# vehicle.net
KiCad netlist of a schematic drawn in Altium Designer
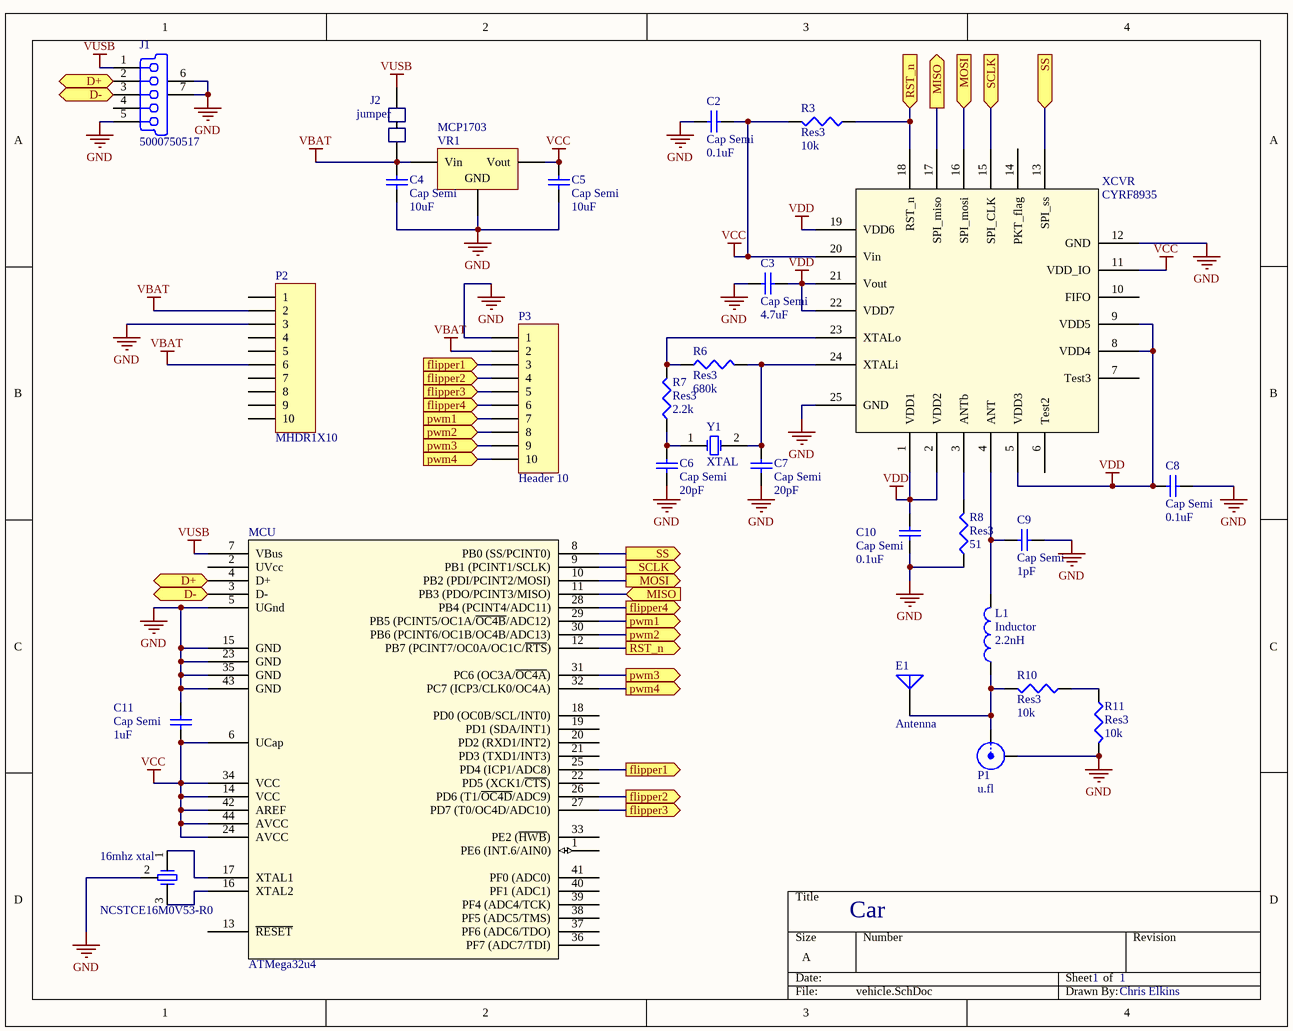
[diagram p0: vehicle.SchDoc]

(export (version "E")
  (design (tool "Eeschema 10.0.6"))
  (components
    (comp (ref "16mhz xtal")
      (value "NCSTCE16M0V53-R0")
      (footprint "OSC")
      (libsource (lib "Integrated_Library1") (part "NCSTCE16M0V53-R0"))
    )
    (comp (ref "C2")
      (value "Cap Semi")
      (footprint "CAPC1608L")
      (description "Capacitor (Semiconductor SIM Model)")
      (fields (field (name "ALTIUM_VALUE") "0.1uF") (field (name "PUBLISHER") "Altium Limited"))
      (libsource (lib "Miscellaneous Devices") (part "Cap Semi"))
    )
    (comp (ref "C3")
      (value "Cap Semi")
      (footprint "CAPC1608L")
      (description "Capacitor (Semiconductor SIM Model)")
      (fields (field (name "ALTIUM_VALUE") "4.7uF") (field (name "PUBLISHER") "Altium Limited"))
      (libsource (lib "Miscellaneous Devices") (part "Cap Semi"))
    )
    (comp (ref "C4")
      (value "Cap Semi")
      (footprint "CAPC1608L")
      (description "Capacitor (Semiconductor SIM Model)")
      (fields (field (name "ALTIUM_VALUE") "10uF") (field (name "PUBLISHER") "Altium Limited"))
      (libsource (lib "Miscellaneous Devices") (part "Cap Semi"))
    )
    (comp (ref "C5")
      (value "Cap Semi")
      (footprint "CAPC1608L")
      (description "Capacitor (Semiconductor SIM Model)")
      (fields (field (name "ALTIUM_VALUE") "10uF") (field (name "PUBLISHER") "Altium Limited"))
      (libsource (lib "Miscellaneous Devices") (part "Cap Semi"))
    )
    (comp (ref "C6")
      (value "Cap Semi")
      (footprint "CAPC1608L")
      (description "Capacitor (Semiconductor SIM Model)")
      (fields (field (name "ALTIUM_VALUE") "20pF") (field (name "PUBLISHER") "Altium Limited"))
      (libsource (lib "Miscellaneous Devices") (part "Cap Semi"))
    )
    (comp (ref "C7")
      (value "Cap Semi")
      (footprint "CAPC1608L")
      (description "Capacitor (Semiconductor SIM Model)")
      (fields (field (name "ALTIUM_VALUE") "20pF") (field (name "PUBLISHER") "Altium Limited"))
      (libsource (lib "Miscellaneous Devices") (part "Cap Semi"))
    )
    (comp (ref "C8")
      (value "Cap Semi")
      (footprint "CAPC1608L")
      (description "Capacitor (Semiconductor SIM Model)")
      (fields (field (name "ALTIUM_VALUE") "0.1uF") (field (name "PUBLISHER") "Altium Limited"))
      (libsource (lib "Miscellaneous Devices") (part "Cap Semi"))
    )
    (comp (ref "C9")
      (value "Cap Semi")
      (footprint "CAPC1608L")
      (description "Capacitor (Semiconductor SIM Model)")
      (fields (field (name "ALTIUM_VALUE") "1pF") (field (name "PUBLISHER") "Altium Limited"))
      (libsource (lib "Miscellaneous Devices") (part "Cap Semi"))
    )
    (comp (ref "C10")
      (value "Cap Semi")
      (footprint "CAPC1608L")
      (description "Capacitor (Semiconductor SIM Model)")
      (fields (field (name "ALTIUM_VALUE") "0.1uF") (field (name "PUBLISHER") "Altium Limited"))
      (libsource (lib "Miscellaneous Devices") (part "Cap Semi"))
    )
    (comp (ref "C11")
      (value "Cap Semi")
      (footprint "CAPC1608L")
      (description "Capacitor (Semiconductor SIM Model)")
      (fields (field (name "ALTIUM_VALUE") "1uF") (field (name "PUBLISHER") "Altium Limited"))
      (libsource (lib "Miscellaneous Devices") (part "Cap Semi"))
    )
    (comp (ref "E1")
      (value "Antenna")
      (footprint "PIN1")
      (description "Generic Antenna")
      (fields (field (name "PUBLISHER") "Altium Limited"))
      (libsource (lib "Miscellaneous Devices") (part "Antenna"))
    )
    (comp (ref "J1")
      (value "5000750517")
      (footprint "HDR1X4")
      (fields (field (name "PUBLISHER") "Altium Limited"))
      (libsource (lib "Molex Serial Bus Mini USB") (part "5000750517"))
    )
    (comp (ref "J2")
      (value "jumper")
      (footprint "jumper pad")
      (libsource (lib "Integrated_Library1") (part "solder jumper"))
    )
    (comp (ref "L1")
      (value "Inductor")
      (footprint "INDC1608L")
      (fields (field (name "ALTIUM_VALUE") "2.2nH") (field (name "PUBLISHER") "Altium Limited"))
      (libsource (lib "Miscellaneous Devices") (part "Inductor"))
    )
    (comp (ref "MCU")
      (value "ATMega32u4")
      (footprint "TQFP44_M")
      (description "usb enabled avr microcontroller")
      (libsource (lib "Integrated_Library1") (part "ATMega32u4"))
    )
    (comp (ref "P1")
      (value "u.fl")
      (footprint "U.FL connector")
      (description "BNC Elbow Connector")
      (fields (field (name "PUBLISHER") "Altium Limited"))
      (libsource (lib "Miscellaneous Connectors") (part "BNC"))
    )
    (comp (ref "P2")
      (value "MHDR1X10")
      (footprint "MHDR1X10")
      (description "Header, 10-Pin")
      (fields (field (name "PUBLISHER") "Altium Limited"))
      (libsource (lib "Miscellaneous Connectors") (part "MHDR1X10"))
    )
    (comp (ref "P3")
      (value "Header 10")
      (footprint "HDR1X10")
      (description "Header, 10-Pin")
      (fields (field (name "PUBLISHER") "Altium Limited"))
      (libsource (lib "Miscellaneous Connectors") (part "Header 10"))
    )
    (comp (ref "R3")
      (value "Res3")
      (footprint "RESC1608L")
      (description "Resistor")
      (fields (field (name "ALTIUM_VALUE") "10k") (field (name "PUBLISHER") "Altium Limited"))
      (libsource (lib "Miscellaneous Devices") (part "Res3"))
    )
    (comp (ref "R6")
      (value "Res3")
      (footprint "RESC1608L")
      (description "Resistor")
      (fields (field (name "ALTIUM_VALUE") "680k") (field (name "PUBLISHER") "Altium Limited"))
      (libsource (lib "Miscellaneous Devices") (part "Res3"))
    )
    (comp (ref "R7")
      (value "Res3")
      (footprint "RESC1608L")
      (description "Resistor")
      (fields (field (name "ALTIUM_VALUE") "2.2k") (field (name "PUBLISHER") "Altium Limited"))
      (libsource (lib "Miscellaneous Devices") (part "Res3"))
    )
    (comp (ref "R8")
      (value "Res3")
      (footprint "RESC1608L")
      (description "Resistor")
      (fields (field (name "ALTIUM_VALUE") "51") (field (name "PUBLISHER") "Altium Limited"))
      (libsource (lib "Miscellaneous Devices") (part "Res3"))
    )
    (comp (ref "R10")
      (value "Res3")
      (footprint "RESC1608L")
      (description "Resistor")
      (fields (field (name "ALTIUM_VALUE") "10k") (field (name "PUBLISHER") "Altium Limited"))
      (libsource (lib "Miscellaneous Devices") (part "Res3"))
    )
    (comp (ref "R11")
      (value "Res3")
      (footprint "RESC1608L")
      (description "Resistor")
      (fields (field (name "ALTIUM_VALUE") "10k") (field (name "PUBLISHER") "Altium Limited"))
      (libsource (lib "Miscellaneous Devices") (part "Res3"))
    )
    (comp (ref "VR1")
      (value "MCP1703")
      (footprint "SOT223-4N")
      (description "Voltage Regulator")
      (fields (field (name "PUBLISHER") "Altium Limited"))
      (libsource (lib "Miscellaneous Devices") (part "Volt Reg"))
    )
    (comp (ref "XCVR")
      (value "CYRF8935")
      (footprint "QFN50P400X400-24VAL")
      (libsource (lib "Integrated_Library1") (part "CYRF8935"))
    )
    (comp (ref "Y1")
      (value "XTAL")
      (footprint "PCBComponent_1")
      (description "Crystal Oscillator")
      (fields (field (name "PUBLISHER") "Altium Limited"))
      (libsource (lib "Miscellaneous Devices") (part "XTAL"))
    )
  )
  (nets
    (net (code "1") (name "/D+") (class "Default")
      (node (ref "J1") (pin "2") (pinfunction "D-_2") (pintype "passive"))
      (node (ref "MCU") (pin "4") (pinfunction "D+_4") (pintype "passive"))
    )
    (net (code "2") (name "/D-") (class "Default")
      (node (ref "J1") (pin "3") (pinfunction "D+_3") (pintype "passive"))
      (node (ref "MCU") (pin "3") (pinfunction "D-_3") (pintype "passive"))
    )
    (net (code "3") (name "/MISO") (class "Default")
      (node (ref "MCU") (pin "11") (pinfunction "PB3_(PDO/PCINT3/MISO)_11") (pintype "passive"))
      (node (ref "XCVR") (pin "17") (pinfunction "SPI_miso_17") (pintype "passive"))
    )
    (net (code "4") (name "/MOSI") (class "Default")
      (node (ref "MCU") (pin "10") (pinfunction "PB2_(PDI/PCINT2/MOSI)_10") (pintype "passive"))
      (node (ref "XCVR") (pin "16") (pinfunction "SPI_mosi_16") (pintype "passive"))
    )
    (net (code "5") (name "/RST_n") (class "Default")
      (node (ref "MCU") (pin "12") (pinfunction "PB7_(PCINT7/OC0A/OC1C/~{RTS})_12") (pintype "passive"))
      (node (ref "R3") (pin "1") (pinfunction "1_1") (pintype "passive"))
      (node (ref "XCVR") (pin "18") (pinfunction "RST_n_18") (pintype "passive"))
    )
    (net (code "6") (name "/SCLK") (class "Default")
      (node (ref "MCU") (pin "9") (pinfunction "PB1_(PCINT1/SCLK)_9") (pintype "passive"))
      (node (ref "XCVR") (pin "15") (pinfunction "SPI_CLK_15") (pintype "passive"))
    )
    (net (code "7") (name "/SS") (class "Default")
      (node (ref "MCU") (pin "8") (pinfunction "PB0_(SS/PCINT0)_8") (pintype "passive"))
      (node (ref "XCVR") (pin "13") (pinfunction "SPI_ss_13") (pintype "passive"))
    )
    (net (code "8") (name "/flipper1") (class "Default")
      (node (ref "MCU") (pin "25") (pinfunction "PD4_(ICP1/ADC8)_25") (pintype "passive"))
      (node (ref "P3") (pin "3") (pinfunction "3_3") (pintype "passive"))
    )
    (net (code "9") (name "/flipper2") (class "Default")
      (node (ref "MCU") (pin "26") (pinfunction "PD6_(T1/~{OC4D}/ADC9)_26") (pintype "passive"))
      (node (ref "P3") (pin "4") (pinfunction "4_4") (pintype "passive"))
    )
    (net (code "10") (name "/flipper3") (class "Default")
      (node (ref "MCU") (pin "27") (pinfunction "PD7_(T0/OC4D/ADC10)_27") (pintype "passive"))
      (node (ref "P3") (pin "5") (pinfunction "5_5") (pintype "passive"))
    )
    (net (code "11") (name "/flipper4") (class "Default")
      (node (ref "MCU") (pin "28") (pinfunction "PB4_(PCINT4/ADC11)_28") (pintype "passive"))
      (node (ref "P3") (pin "6") (pinfunction "6_6") (pintype "passive"))
    )
    (net (code "12") (name "/pwm1") (class "Default")
      (node (ref "MCU") (pin "29") (pinfunction "PB5_(PCINT5/OC1A/~{OC4B}/ADC12)_29") (pintype "passive"))
      (node (ref "P3") (pin "7") (pinfunction "7_7") (pintype "passive"))
    )
    (net (code "13") (name "/pwm2") (class "Default")
      (node (ref "MCU") (pin "30") (pinfunction "PB6_(PCINT6/OC1B/OC4B/ADC13)_30") (pintype "passive"))
      (node (ref "P3") (pin "8") (pinfunction "8_8") (pintype "passive"))
    )
    (net (code "14") (name "/pwm3") (class "Default")
      (node (ref "MCU") (pin "31") (pinfunction "PC6_(OC3A/~{OC4A})_31") (pintype "passive"))
      (node (ref "P3") (pin "9") (pinfunction "9_9") (pintype "passive"))
    )
    (net (code "15") (name "/pwm4") (class "Default")
      (node (ref "MCU") (pin "32") (pinfunction "PC7_(ICP3/CLK0/OC4A)_32") (pintype "passive"))
      (node (ref "P3") (pin "10") (pinfunction "10_10") (pintype "passive"))
    )
    (net (code "16") (name "GND") (class "Default")
      (node (ref "16mhz xtal") (pin "2") (pintype "passive"))
      (node (ref "C10") (pin "2") (pinfunction "2_2") (pintype "passive"))
      (node (ref "C11") (pin "2") (pinfunction "2_2") (pintype "passive"))
      (node (ref "C2") (pin "1") (pinfunction "1_1") (pintype "passive"))
      (node (ref "C3") (pin "1") (pinfunction "1_1") (pintype "passive"))
      (node (ref "C4") (pin "1") (pinfunction "1_1") (pintype "passive"))
      (node (ref "C5") (pin "1") (pinfunction "1_1") (pintype "passive"))
      (node (ref "C6") (pin "1") (pinfunction "1_1") (pintype "passive"))
      (node (ref "C7") (pin "1") (pinfunction "1_1") (pintype "passive"))
      (node (ref "C8") (pin "1") (pinfunction "1_1") (pintype "passive"))
      (node (ref "C9") (pin "2") (pinfunction "2_2") (pintype "passive"))
      (node (ref "J1") (pin "5") (pinfunction "GND_5") (pintype "passive"))
      (node (ref "J1") (pin "6") (pinfunction "MH1_6") (pintype "passive"))
      (node (ref "J1") (pin "7") (pinfunction "MH2_7") (pintype "passive"))
      (node (ref "MCU") (pin "15") (pinfunction "GND_15") (pintype "passive"))
      (node (ref "MCU") (pin "23") (pinfunction "GND_23") (pintype "passive"))
      (node (ref "MCU") (pin "35") (pinfunction "GND_35") (pintype "passive"))
      (node (ref "MCU") (pin "43") (pinfunction "GND_43") (pintype "passive"))
      (node (ref "MCU") (pin "5") (pinfunction "UGnd_5") (pintype "passive"))
      (node (ref "P1") (pin "2") (pinfunction "Y_2") (pintype "passive"))
      (node (ref "P2") (pin "3") (pinfunction "3_3") (pintype "passive"))
      (node (ref "P3") (pin "1") (pinfunction "1_1") (pintype "passive"))
      (node (ref "R11") (pin "2") (pinfunction "2_2") (pintype "passive"))
      (node (ref "R8") (pin "1") (pinfunction "1_1") (pintype "passive"))
      (node (ref "VR1") (pin "2") (pinfunction "GND_2") (pintype "passive"))
      (node (ref "XCVR") (pin "12") (pinfunction "GND_12") (pintype "passive"))
      (node (ref "XCVR") (pin "25") (pinfunction "GND_25") (pintype "passive"))
    )
    (net (code "17") (name "Net-(E1-A)") (class "Default")
      (node (ref "E1") (pin "1") (pinfunction "A_1") (pintype "passive"))
      (node (ref "L1") (pin "1") (pinfunction "1_1") (pintype "passive"))
      (node (ref "P1") (pin "1") (pinfunction "X_1") (pintype "passive"))
      (node (ref "R10") (pin "2") (pinfunction "2_2") (pintype "passive"))
    )
    (net (code "18") (name "Net-(MCU-XTAL1)") (class "Default")
      (node (ref "16mhz xtal") (pin "1") (pintype "passive"))
      (node (ref "MCU") (pin "17") (pinfunction "XTAL1_17") (pintype "passive"))
    )
    (net (code "19") (name "Net-(MCU-XTAL2)") (class "Default")
      (node (ref "16mhz xtal") (pin "3") (pintype "passive"))
      (node (ref "MCU") (pin "16") (pinfunction "XTAL2_16") (pintype "passive"))
    )
    (net (code "20") (name "Net-(R10-Pad1)") (class "Default")
      (node (ref "R10") (pin "1") (pinfunction "1_1") (pintype "passive"))
      (node (ref "R11") (pin "1") (pinfunction "1_1") (pintype "passive"))
    )
    (net (code "21") (name "Net-(XCVR-ANT)") (class "Default")
      (node (ref "C9") (pin "1") (pinfunction "1_1") (pintype "passive"))
      (node (ref "L1") (pin "2") (pinfunction "2_2") (pintype "passive"))
      (node (ref "XCVR") (pin "4") (pinfunction "ANT_4") (pintype "passive"))
    )
    (net (code "22") (name "Net-(XCVR-ANTb)") (class "Default")
      (node (ref "R8") (pin "2") (pinfunction "2_2") (pintype "passive"))
      (node (ref "XCVR") (pin "3") (pinfunction "ANTb_3") (pintype "passive"))
    )
    (net (code "23") (name "Net-(XCVR-XTALi)") (class "Default")
      (node (ref "C7") (pin "2") (pinfunction "2_2") (pintype "passive"))
      (node (ref "R6") (pin "2") (pinfunction "2_2") (pintype "passive"))
      (node (ref "XCVR") (pin "24") (pinfunction "XTALi_24") (pintype "passive"))
      (node (ref "Y1") (pin "2") (pinfunction "OSC2_2") (pintype "passive"))
    )
    (net (code "24") (name "Net-(XCVR-XTALo)") (class "Default")
      (node (ref "R6") (pin "1") (pinfunction "1_1") (pintype "passive"))
      (node (ref "R7") (pin "2") (pinfunction "2_2") (pintype "passive"))
      (node (ref "XCVR") (pin "23") (pinfunction "XTALo_23") (pintype "passive"))
    )
    (net (code "25") (name "Net-(Y1-OSC1)") (class "Default")
      (node (ref "C6") (pin "2") (pinfunction "2_2") (pintype "passive"))
      (node (ref "R7") (pin "1") (pinfunction "1_1") (pintype "passive"))
      (node (ref "Y1") (pin "1") (pinfunction "OSC1_1") (pintype "passive"))
    )
    (net (code "26") (name "VBAT") (class "Default")
      (node (ref "C4") (pin "2") (pinfunction "2_2") (pintype "passive"))
      (node (ref "J2") (pin "2") (pintype "passive"))
      (node (ref "P2") (pin "2") (pinfunction "2_2") (pintype "passive"))
      (node (ref "P2") (pin "6") (pinfunction "6_6") (pintype "passive"))
      (node (ref "P3") (pin "2") (pinfunction "2_2") (pintype "passive"))
      (node (ref "VR1") (pin "1") (pinfunction "Vin_1") (pintype "passive"))
    )
    (net (code "27") (name "VCC") (class "Default")
      (node (ref "C11") (pin "1") (pinfunction "1_1") (pintype "passive"))
      (node (ref "C2") (pin "2") (pinfunction "2_2") (pintype "passive"))
      (node (ref "C5") (pin "2") (pinfunction "2_2") (pintype "passive"))
      (node (ref "MCU") (pin "14") (pinfunction "VCC_14") (pintype "passive"))
      (node (ref "MCU") (pin "24") (pinfunction "AVCC_24") (pintype "passive"))
      (node (ref "MCU") (pin "34") (pinfunction "VCC_34") (pintype "passive"))
      (node (ref "MCU") (pin "42") (pinfunction "AREF_42") (pintype "passive"))
      (node (ref "MCU") (pin "44") (pinfunction "AVCC_44") (pintype "passive"))
      (node (ref "MCU") (pin "6") (pinfunction "UCap_6") (pintype "passive"))
      (node (ref "R3") (pin "2") (pinfunction "2_2") (pintype "passive"))
      (node (ref "VR1") (pin "3") (pinfunction "Vout_3") (pintype "passive"))
      (node (ref "XCVR") (pin "11") (pinfunction "VDD_IO_11") (pintype "passive"))
      (node (ref "XCVR") (pin "20") (pinfunction "Vin_20") (pintype "passive"))
    )
    (net (code "28") (name "VDD") (class "Default")
      (node (ref "C10") (pin "1") (pinfunction "1_1") (pintype "passive"))
      (node (ref "C3") (pin "2") (pinfunction "2_2") (pintype "passive"))
      (node (ref "C8") (pin "2") (pinfunction "2_2") (pintype "passive"))
      (node (ref "XCVR") (pin "1") (pinfunction "VDD1_1") (pintype "passive"))
      (node (ref "XCVR") (pin "19") (pinfunction "VDD6_19") (pintype "passive"))
      (node (ref "XCVR") (pin "2") (pinfunction "VDD2_2") (pintype "passive"))
      (node (ref "XCVR") (pin "21") (pinfunction "Vout_21") (pintype "passive"))
      (node (ref "XCVR") (pin "22") (pinfunction "VDD7_22") (pintype "passive"))
      (node (ref "XCVR") (pin "5") (pinfunction "VDD3_5") (pintype "passive"))
      (node (ref "XCVR") (pin "8") (pinfunction "VDD4_8") (pintype "passive"))
      (node (ref "XCVR") (pin "9") (pinfunction "VDD5_9") (pintype "passive"))
    )
    (net (code "29") (name "VUSB") (class "Default")
      (node (ref "J1") (pin "1") (pinfunction "V_BUS_1") (pintype "passive"))
      (node (ref "J2") (pin "1") (pintype "passive"))
      (node (ref "MCU") (pin "7") (pinfunction "VBus_7") (pintype "passive"))
    )
    (net (code "30") (name "unconnected-(J1-ID-Pad4)") (class "Default")
      (node (ref "J1") (pin "4") (pinfunction "ID_4") (pintype "passive"))
    )
    (net (code "31") (name "unconnected-(MCU-PD0_(OC0B{slash}SCL{slash}INT0)-Pad18)") (class "Default")
      (node (ref "MCU") (pin "18") (pinfunction "PD0_(OC0B/SCL/INT0)_18") (pintype "passive"))
    )
    (net (code "32") (name "unconnected-(MCU-PD1_(SDA{slash}INT1)-Pad19)") (class "Default")
      (node (ref "MCU") (pin "19") (pinfunction "PD1_(SDA/INT1)_19") (pintype "passive"))
    )
    (net (code "33") (name "unconnected-(MCU-PD2_(RXD1{slash}INT2)-Pad20)") (class "Default")
      (node (ref "MCU") (pin "20") (pinfunction "PD2_(RXD1/INT2)_20") (pintype "passive"))
    )
    (net (code "34") (name "unconnected-(MCU-PD3_(TXD1{slash}INT3)-Pad21)") (class "Default")
      (node (ref "MCU") (pin "21") (pinfunction "PD3_(TXD1/INT3)_21") (pintype "passive"))
    )
    (net (code "35") (name "unconnected-(MCU-PD5_(XCK1{slash}~{CTS})-Pad22)") (class "Default")
      (node (ref "MCU") (pin "22") (pinfunction "PD5_(XCK1/~{CTS})_22") (pintype "passive"))
    )
    (net (code "36") (name "unconnected-(MCU-PE2_(~{HWB})-Pad33)") (class "Default")
      (node (ref "MCU") (pin "33") (pinfunction "PE2_(~{HWB})_33") (pintype "passive"))
    )
    (net (code "37") (name "unconnected-(MCU-PE6_(INT.6{slash}AIN0)-Pad1)") (class "Default")
      (node (ref "MCU") (pin "1") (pinfunction "PE6_(INT.6/AIN0)_1") (pintype "bidirectional"))
    )
    (net (code "38") (name "unconnected-(MCU-PF0_(ADC0)-Pad41)") (class "Default")
      (node (ref "MCU") (pin "41") (pinfunction "PF0_(ADC0)_41") (pintype "passive"))
    )
    (net (code "39") (name "unconnected-(MCU-PF1_(ADC1)-Pad40)") (class "Default")
      (node (ref "MCU") (pin "40") (pinfunction "PF1_(ADC1)_40") (pintype "passive"))
    )
    (net (code "40") (name "unconnected-(MCU-PF4_(ADC4{slash}TCK)-Pad39)") (class "Default")
      (node (ref "MCU") (pin "39") (pinfunction "PF4_(ADC4/TCK)_39") (pintype "passive"))
    )
    (net (code "41") (name "unconnected-(MCU-PF5_(ADC5{slash}TMS)-Pad38)") (class "Default")
      (node (ref "MCU") (pin "38") (pinfunction "PF5_(ADC5/TMS)_38") (pintype "passive"))
    )
    (net (code "42") (name "unconnected-(MCU-PF6_(ADC6{slash}TDO)-Pad37)") (class "Default")
      (node (ref "MCU") (pin "37") (pinfunction "PF6_(ADC6/TDO)_37") (pintype "passive"))
    )
    (net (code "43") (name "unconnected-(MCU-PF7_(ADC7{slash}TDI)-Pad36)") (class "Default")
      (node (ref "MCU") (pin "36") (pinfunction "PF7_(ADC7/TDI)_36") (pintype "passive"))
    )
    (net (code "44") (name "unconnected-(MCU-UVcc-Pad2)") (class "Default")
      (node (ref "MCU") (pin "2") (pinfunction "UVcc_2") (pintype "power_in"))
    )
    (net (code "45") (name "unconnected-(MCU-~{RESET}-Pad13)") (class "Default")
      (node (ref "MCU") (pin "13") (pinfunction "~{RESET}_13") (pintype "passive"))
    )
    (net (code "46") (name "unconnected-(P2-Pad1)") (class "Default")
      (node (ref "P2") (pin "1") (pinfunction "1_1") (pintype "passive"))
    )
    (net (code "47") (name "unconnected-(P2-Pad4)") (class "Default")
      (node (ref "P2") (pin "4") (pinfunction "4_4") (pintype "passive"))
    )
    (net (code "48") (name "unconnected-(P2-Pad5)") (class "Default")
      (node (ref "P2") (pin "5") (pinfunction "5_5") (pintype "passive"))
    )
    (net (code "49") (name "unconnected-(P2-Pad7)") (class "Default")
      (node (ref "P2") (pin "7") (pinfunction "7_7") (pintype "passive"))
    )
    (net (code "50") (name "unconnected-(P2-Pad8)") (class "Default")
      (node (ref "P2") (pin "8") (pinfunction "8_8") (pintype "passive"))
    )
    (net (code "51") (name "unconnected-(P2-Pad9)") (class "Default")
      (node (ref "P2") (pin "9") (pinfunction "9_9") (pintype "passive"))
    )
    (net (code "52") (name "unconnected-(P2-Pad10)") (class "Default")
      (node (ref "P2") (pin "10") (pinfunction "10_10") (pintype "passive"))
    )
    (net (code "53") (name "unconnected-(XCVR-FIFO-Pad10)") (class "Default")
      (node (ref "XCVR") (pin "10") (pinfunction "FIFO_10") (pintype "passive"))
    )
    (net (code "54") (name "unconnected-(XCVR-PKT_flag-Pad14)") (class "Default")
      (node (ref "XCVR") (pin "14") (pinfunction "PKT_flag_14") (pintype "passive"))
    )
    (net (code "55") (name "unconnected-(XCVR-Test2-Pad6)") (class "Default")
      (node (ref "XCVR") (pin "6") (pinfunction "Test2_6") (pintype "passive"))
    )
    (net (code "56") (name "unconnected-(XCVR-Test3-Pad7)") (class "Default")
      (node (ref "XCVR") (pin "7") (pinfunction "Test3_7") (pintype "passive"))
    )
  )
)
